# polarshield3_0c.net
KiCad netlist of a schematic drawn in EAGLE
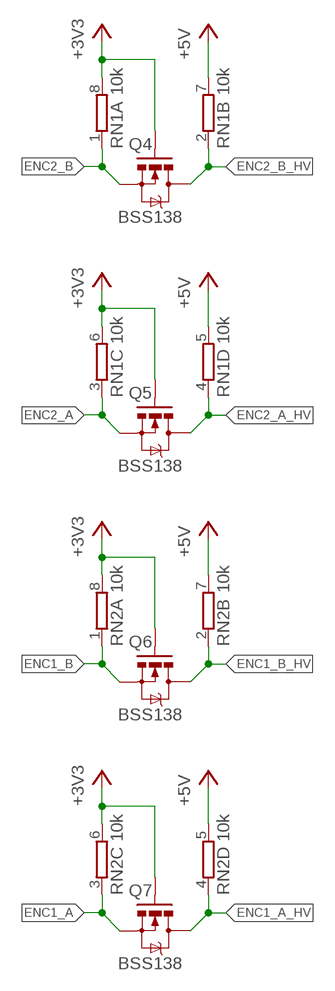
[diagram p0: schematic, sheet 1, part 1 of 2]
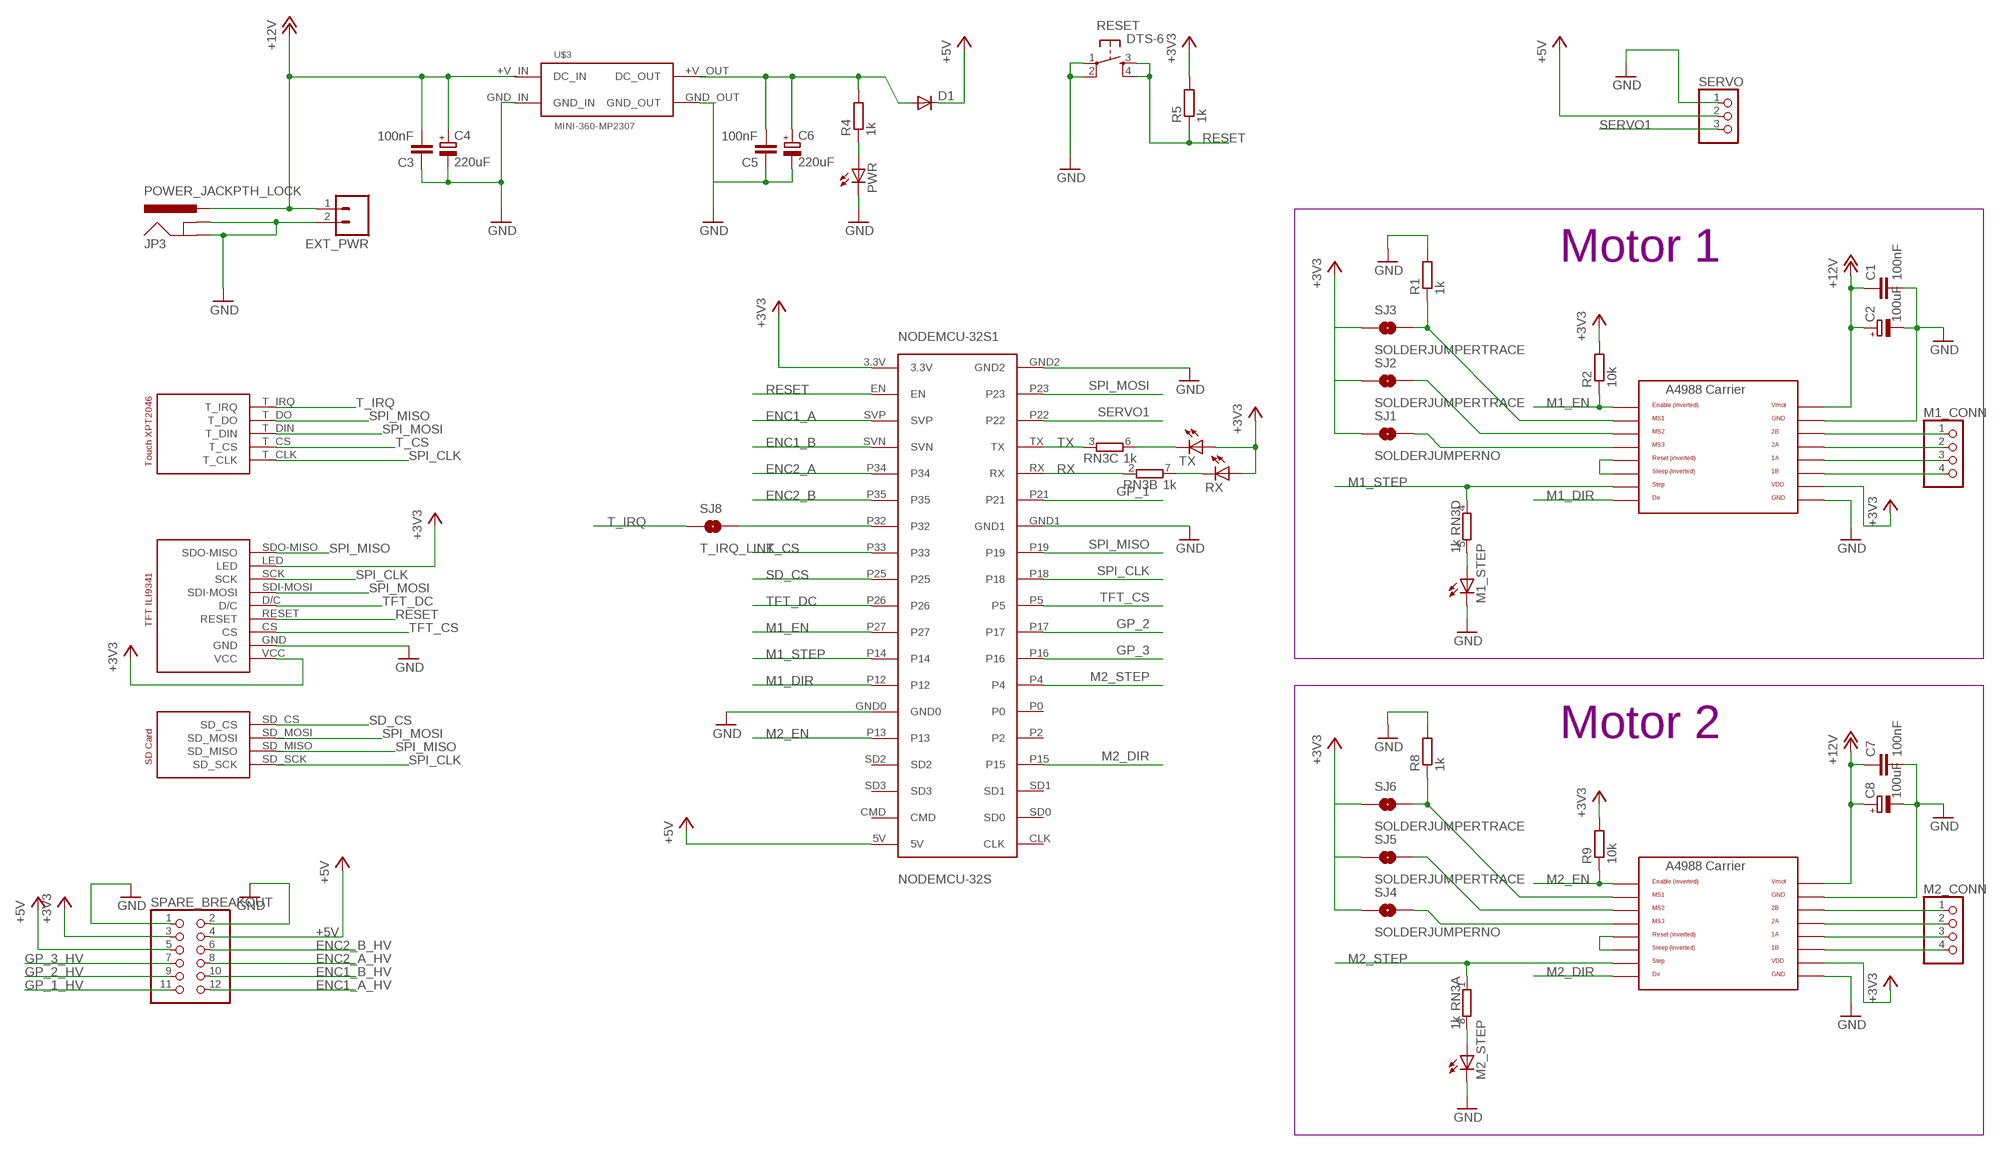
[diagram p1: schematic, sheet 1, part 2 of 2]

(export (version "E")
  (design (tool "Eeschema 10.0.6"))
  (components
    (comp (ref "C1")
      (value "100nF")
      (footprint "eagle-import:C0805")
      (libsource (lib "eagle-import") (part "C-EUC0805"))
    )
    (comp (ref "C2")
      (value "100uF")
      (footprint "eagle-import:153CLV-0605")
      (libsource (lib "eagle-import") (part "CPOL-EU153CLV-0605"))
    )
    (comp (ref "C3")
      (value "100nF")
      (footprint "eagle-import:C0805")
      (libsource (lib "eagle-import") (part "C-EUC0805"))
    )
    (comp (ref "C4")
      (value "220uF")
      (footprint "eagle-import:153CLV-0605")
      (libsource (lib "eagle-import") (part "CPOL-EU153CLV-0605"))
    )
    (comp (ref "C5")
      (value "100nF")
      (footprint "eagle-import:C0805")
      (libsource (lib "eagle-import") (part "C-EUC0805"))
    )
    (comp (ref "C6")
      (value "220uF")
      (footprint "eagle-import:153CLV-0605")
      (libsource (lib "eagle-import") (part "CPOL-EU153CLV-0605"))
    )
    (comp (ref "C7")
      (value "100nF")
      (footprint "eagle-import:C0805")
      (libsource (lib "eagle-import") (part "C-EUC0805"))
    )
    (comp (ref "C8")
      (value "100uF")
      (footprint "eagle-import:153CLV-0605")
      (libsource (lib "eagle-import") (part "CPOL-EU153CLV-0605"))
    )
    (comp (ref "D1")
      (value "DIODE-DO214BA")
      (footprint "eagle-import:DO214BA")
      (libsource (lib "eagle-import") (part "DIODE-DO214BA"))
    )
    (comp (ref "EXT_PWR")
      (value "M02PTH")
      (footprint "eagle-import:1X02")
      (libsource (lib "eagle-import") (part "M02PTH"))
    )
    (comp (ref "JP3")
      (value "POWER_JACKPTH_LOCK")
      (footprint "eagle-import:POWER_JACK_PTH_LOCK")
      (libsource (lib "eagle-import") (part "POWER_JACKPTH_LOCK"))
    )
    (comp (ref "M1_CONN")
      (value "PINHD-1X4/90")
      (footprint "eagle-import:1X04_90")
      (libsource (lib "eagle-import") (part "PINHD-1X4/90"))
    )
    (comp (ref "M1_STEP")
      (value "LEDCHIPLED_0805")
      (footprint "eagle-import:CHIPLED_0805")
      (libsource (lib "eagle-import") (part "LEDCHIPLED_0805"))
    )
    (comp (ref "M2_CONN")
      (value "PINHD-1X4/90")
      (footprint "eagle-import:1X04_90")
      (libsource (lib "eagle-import") (part "PINHD-1X4/90"))
    )
    (comp (ref "M2_STEP")
      (value "LEDCHIPLED_0805")
      (footprint "eagle-import:CHIPLED_0805")
      (libsource (lib "eagle-import") (part "LEDCHIPLED_0805"))
    )
    (comp (ref "MOTOR_1")
      (value "A4988BREAKOUT")
      (footprint "eagle-import:A4988BREAKOUT")
      (libsource (lib "eagle-import") (part "A4988BREAKOUT"))
    )
    (comp (ref "MOTOR_2")
      (value "A4988BREAKOUT")
      (footprint "eagle-import:A4988BREAKOUT")
      (libsource (lib "eagle-import") (part "A4988BREAKOUT"))
    )
    (comp (ref "NODEMCU-32S1")
      (value "NODEMCU-32S")
      (footprint "eagle-import:NODEMCU-32S")
      (libsource (lib "eagle-import") (part "NODEMCU-32S"))
    )
    (comp (ref "PWR")
      (value "LEDCHIPLED_0805")
      (footprint "eagle-import:CHIPLED_0805")
      (libsource (lib "eagle-import") (part "LEDCHIPLED_0805"))
    )
    (comp (ref "Q4")
      (value "BSS138")
      (footprint "eagle-import:SOT23-3")
      (libsource (lib "eagle-import") (part "MOSFET-NCHANNELSMD"))
    )
    (comp (ref "Q5")
      (value "BSS138")
      (footprint "eagle-import:SOT23-3")
      (libsource (lib "eagle-import") (part "MOSFET-NCHANNELSMD"))
    )
    (comp (ref "Q6")
      (value "BSS138")
      (footprint "eagle-import:SOT23-3")
      (libsource (lib "eagle-import") (part "MOSFET-NCHANNELSMD"))
    )
    (comp (ref "Q7")
      (value "BSS138")
      (footprint "eagle-import:SOT23-3")
      (libsource (lib "eagle-import") (part "MOSFET-NCHANNELSMD"))
    )
    (comp (ref "R1")
      (value "1k")
      (footprint "eagle-import:M0805")
      (libsource (lib "eagle-import") (part "R-EU_M0805"))
    )
    (comp (ref "R2")
      (value "10k")
      (footprint "eagle-import:M0805")
      (libsource (lib "eagle-import") (part "R-EU_M0805"))
    )
    (comp (ref "R4")
      (value "1k")
      (footprint "eagle-import:M0805")
      (libsource (lib "eagle-import") (part "R-EU_M0805"))
    )
    (comp (ref "R5")
      (value "1k")
      (footprint "eagle-import:M0805")
      (libsource (lib "eagle-import") (part "R-EU_M0805"))
    )
    (comp (ref "R8")
      (value "1k")
      (footprint "eagle-import:M0805")
      (libsource (lib "eagle-import") (part "R-EU_M0805"))
    )
    (comp (ref "R9")
      (value "10k")
      (footprint "eagle-import:M0805")
      (libsource (lib "eagle-import") (part "R-EU_M0805"))
    )
    (comp (ref "RESET")
      (value "DTS-6")
      (footprint "eagle-import:DTS-6")
      (libsource (lib "eagle-import") (part "DTS-6"))
    )
    (comp (ref "RN1")
      (value "10k")
      (footprint "eagle-import:EXB38V")
      (libsource (lib "eagle-import") (part "4R-NEXB38V"))
    )
    (comp (ref "RN2")
      (value "10k")
      (footprint "eagle-import:EXB38V")
      (libsource (lib "eagle-import") (part "4R-NEXB38V"))
    )
    (comp (ref "RN3")
      (value "1k")
      (footprint "eagle-import:EXB38V")
      (libsource (lib "eagle-import") (part "4R-NEXB38V"))
    )
    (comp (ref "RX")
      (value "LEDCHIPLED_0805")
      (footprint "eagle-import:CHIPLED_0805")
      (libsource (lib "eagle-import") (part "LEDCHIPLED_0805"))
    )
    (comp (ref "SERVO")
      (value "PINHD-1X3/90")
      (footprint "eagle-import:1X03_90")
      (libsource (lib "eagle-import") (part "PINHD-1X3/90"))
    )
    (comp (ref "SJ1")
      (value "SOLDERJUMPERNO")
      (footprint "eagle-import:SJ_2S-NO")
      (libsource (lib "eagle-import") (part "polargraph3_SOLDERJUMPERNO"))
    )
    (comp (ref "SJ2")
      (value "SOLDERJUMPERTRACE")
      (footprint "eagle-import:SJ_2S-TRACE")
      (libsource (lib "eagle-import") (part "polargraph3_SOLDERJUMPERTRACE"))
    )
    (comp (ref "SJ3")
      (value "SOLDERJUMPERTRACE")
      (footprint "eagle-import:SJ_2S-TRACE")
      (libsource (lib "eagle-import") (part "polargraph3_SOLDERJUMPERTRACE"))
    )
    (comp (ref "SJ4")
      (value "SOLDERJUMPERNO")
      (footprint "eagle-import:SJ_2S-NO")
      (libsource (lib "eagle-import") (part "polargraph3_SOLDERJUMPERNO"))
    )
    (comp (ref "SJ5")
      (value "SOLDERJUMPERTRACE")
      (footprint "eagle-import:SJ_2S-TRACE")
      (libsource (lib "eagle-import") (part "polargraph3_SOLDERJUMPERTRACE"))
    )
    (comp (ref "SJ6")
      (value "SOLDERJUMPERTRACE")
      (footprint "eagle-import:SJ_2S-TRACE")
      (libsource (lib "eagle-import") (part "polargraph3_SOLDERJUMPERTRACE"))
    )
    (comp (ref "SJ8")
      (value "T_IRQ_LINK")
      (footprint "eagle-import:SJ_2S-NO")
      (libsource (lib "eagle-import") (part "SOLDERJUMPERNO"))
    )
    (comp (ref "SPARE_BREAKOUT")
      (value "PINHD-2X6")
      (footprint "eagle-import:2X06")
      (libsource (lib "eagle-import") (part "PINHD-2X6"))
    )
    (comp (ref "TX")
      (value "LEDCHIPLED_0805")
      (footprint "eagle-import:CHIPLED_0805")
      (libsource (lib "eagle-import") (part "LEDCHIPLED_0805"))
    )
    (comp (ref "U$2")
      (value "2.4_TFT_SPI_TOUCH_SD")
      (footprint "eagle-import:2.4_TFT_SPI_TOUCH_SD")
      (libsource (lib "eagle-import") (part "2.4_TFT_SPI_TOUCH_SD"))
    )
    (comp (ref "U$3")
      (value "MINI-360-MP2307")
      (footprint "eagle-import:MINI-360-MP2307")
      (libsource (lib "eagle-import") (part "MINI-360-MP2307"))
    )
  )
  (nets
    (net (code "1") (name "+3V3") (class "Default")
      (node (ref "MOTOR_1") (pin "VDD") (pinfunction "VDD_VDD") (pintype "power_in"))
      (node (ref "MOTOR_2") (pin "VDD") (pinfunction "VDD_VDD") (pintype "power_in"))
      (node (ref "NODEMCU-32S1") (pin "3.3V") (pinfunction "3.3V_3.3V") (pintype "bidirectional"))
      (node (ref "Q4") (pin "1") (pinfunction "G_1") (pintype "passive"))
      (node (ref "Q5") (pin "1") (pinfunction "G_1") (pintype "passive"))
      (node (ref "Q6") (pin "1") (pinfunction "G_1") (pintype "passive"))
      (node (ref "Q7") (pin "1") (pinfunction "G_1") (pintype "passive"))
      (node (ref "R2") (pin "2") (pinfunction "2_2") (pintype "passive"))
      (node (ref "R5") (pin "2") (pinfunction "2_2") (pintype "passive"))
      (node (ref "R9") (pin "2") (pinfunction "2_2") (pintype "passive"))
      (node (ref "RN1") (pin "6") (pinfunction "2_6") (pintype "passive"))
      (node (ref "RN1") (pin "8") (pinfunction "2_8") (pintype "passive"))
      (node (ref "RN2") (pin "6") (pinfunction "2_6") (pintype "passive"))
      (node (ref "RN2") (pin "8") (pinfunction "2_8") (pintype "passive"))
      (node (ref "RX") (pin "A") (pinfunction "A_A") (pintype "passive"))
      (node (ref "SJ1") (pin "1") (pinfunction "1_1") (pintype "passive"))
      (node (ref "SJ2") (pin "1") (pinfunction "1_1") (pintype "passive"))
      (node (ref "SJ3") (pin "1") (pinfunction "1_1") (pintype "passive"))
      (node (ref "SJ4") (pin "1") (pinfunction "1_1") (pintype "passive"))
      (node (ref "SJ5") (pin "1") (pinfunction "1_1") (pintype "passive"))
      (node (ref "SJ6") (pin "1") (pinfunction "1_1") (pintype "passive"))
      (node (ref "SPARE_BREAKOUT") (pin "3") (pinfunction "3_3") (pintype "passive"))
      (node (ref "TX") (pin "A") (pinfunction "A_A") (pintype "passive"))
      (node (ref "U$2") (pin "LED") (pinfunction "LED_LED") (pintype "bidirectional"))
      (node (ref "U$2") (pin "VCC") (pinfunction "VCC_VCC") (pintype "bidirectional"))
    )
    (net (code "2") (name "+5V") (class "Default")
      (node (ref "D1") (pin "C") (pinfunction "C_C") (pintype "passive"))
      (node (ref "NODEMCU-32S1") (pin "5V") (pinfunction "5V_5V") (pintype "bidirectional"))
      (node (ref "RN1") (pin "5") (pinfunction "2_5") (pintype "passive"))
      (node (ref "RN1") (pin "7") (pinfunction "2_7") (pintype "passive"))
      (node (ref "RN2") (pin "5") (pinfunction "2_5") (pintype "passive"))
      (node (ref "RN2") (pin "7") (pinfunction "2_7") (pintype "passive"))
      (node (ref "SERVO") (pin "2") (pinfunction "2_2") (pintype "passive"))
      (node (ref "SPARE_BREAKOUT") (pin "4") (pinfunction "4_4") (pintype "passive"))
      (node (ref "SPARE_BREAKOUT") (pin "5") (pinfunction "5_5") (pintype "passive"))
    )
    (net (code "3") (name "+12V") (class "Default")
      (node (ref "C1") (pin "1") (pinfunction "1_1") (pintype "passive"))
      (node (ref "C2") (pin "+") (pinfunction "+_+") (pintype "passive"))
      (node (ref "C3") (pin "2") (pinfunction "2_2") (pintype "passive"))
      (node (ref "C4") (pin "+") (pinfunction "+_+") (pintype "passive"))
      (node (ref "C7") (pin "1") (pinfunction "1_1") (pintype "passive"))
      (node (ref "C8") (pin "+") (pinfunction "+_+") (pintype "passive"))
      (node (ref "EXT_PWR") (pin "1") (pinfunction "1_1") (pintype "passive"))
      (node (ref "JP3") (pin "PWR") (pinfunction "PWR_PWR") (pintype "bidirectional"))
      (node (ref "MOTOR_1") (pin "VMOT") (pinfunction "VMOT_VMOT") (pintype "power_in"))
      (node (ref "MOTOR_2") (pin "VMOT") (pinfunction "VMOT_VMOT") (pintype "power_in"))
      (node (ref "U$3") (pin "+V_IN") (pinfunction "DC_IN_+V_IN") (pintype "bidirectional"))
    )
    (net (code "4") (name "/GP_1") (class "Default")
      (node (ref "NODEMCU-32S1") (pin "P21") (pinfunction "P21_P21") (pintype "bidirectional"))
    )
    (net (code "5") (name "/GP_1_HV") (class "Default")
      (node (ref "SPARE_BREAKOUT") (pin "11") (pinfunction "11_11") (pintype "passive"))
    )
    (net (code "6") (name "/GP_2") (class "Default")
      (node (ref "NODEMCU-32S1") (pin "P17") (pinfunction "P17_P17") (pintype "bidirectional"))
    )
    (net (code "7") (name "/GP_2_HV") (class "Default")
      (node (ref "SPARE_BREAKOUT") (pin "9") (pinfunction "9_9") (pintype "passive"))
    )
    (net (code "8") (name "/GP_3") (class "Default")
      (node (ref "NODEMCU-32S1") (pin "P16") (pinfunction "P16_P16") (pintype "bidirectional"))
    )
    (net (code "9") (name "/GP_3_HV") (class "Default")
      (node (ref "SPARE_BREAKOUT") (pin "7") (pinfunction "7_7") (pintype "passive"))
    )
    (net (code "10") (name "/M1_DIR") (class "Default")
      (node (ref "MOTOR_1") (pin "DIR") (pinfunction "DIR_DIR") (pintype "input"))
      (node (ref "NODEMCU-32S1") (pin "P12") (pinfunction "P12_P12") (pintype "bidirectional"))
    )
    (net (code "11") (name "/M1_EN") (class "Default")
      (node (ref "MOTOR_1") (pin "EN") (pinfunction "EN_EN") (pintype "input"))
      (node (ref "NODEMCU-32S1") (pin "P27") (pinfunction "P27_P27") (pintype "bidirectional"))
      (node (ref "R2") (pin "1") (pinfunction "1_1") (pintype "passive"))
    )
    (net (code "12") (name "/M1_STEP") (class "Default")
      (node (ref "MOTOR_1") (pin "STEP") (pinfunction "STEP_STEP") (pintype "input"))
      (node (ref "NODEMCU-32S1") (pin "P14") (pinfunction "P14_P14") (pintype "bidirectional"))
      (node (ref "RN3") (pin "4") (pinfunction "1_4") (pintype "passive"))
    )
    (net (code "13") (name "/M2_DIR") (class "Default")
      (node (ref "MOTOR_2") (pin "DIR") (pinfunction "DIR_DIR") (pintype "input"))
      (node (ref "NODEMCU-32S1") (pin "P15") (pinfunction "P15_P15") (pintype "bidirectional"))
    )
    (net (code "14") (name "/M2_EN") (class "Default")
      (node (ref "MOTOR_2") (pin "EN") (pinfunction "EN_EN") (pintype "input"))
      (node (ref "NODEMCU-32S1") (pin "P13") (pinfunction "P13_P13") (pintype "bidirectional"))
      (node (ref "R9") (pin "1") (pinfunction "1_1") (pintype "passive"))
    )
    (net (code "15") (name "/M2_STEP") (class "Default")
      (node (ref "MOTOR_2") (pin "STEP") (pinfunction "STEP_STEP") (pintype "input"))
      (node (ref "NODEMCU-32S1") (pin "P4") (pinfunction "P4_P4") (pintype "bidirectional"))
      (node (ref "RN3") (pin "1") (pinfunction "1_1") (pintype "passive"))
    )
    (net (code "16") (name "/RESET") (class "Default")
      (node (ref "NODEMCU-32S1") (pin "EN") (pinfunction "EN_EN") (pintype "bidirectional"))
      (node (ref "R5") (pin "1") (pinfunction "1_1") (pintype "passive"))
      (node (ref "RESET") (pin "3") (pinfunction "3_3") (pintype "passive"))
      (node (ref "RESET") (pin "4") (pinfunction "4_4") (pintype "passive"))
      (node (ref "U$2") (pin "RESET") (pinfunction "RESET_RESET") (pintype "bidirectional"))
    )
    (net (code "17") (name "/RX") (class "Default")
      (node (ref "NODEMCU-32S1") (pin "RX") (pinfunction "RX_RX") (pintype "bidirectional"))
      (node (ref "RN3") (pin "2") (pinfunction "1_2") (pintype "passive"))
    )
    (net (code "18") (name "/SD_CS") (class "Default")
      (node (ref "NODEMCU-32S1") (pin "P25") (pinfunction "P25_P25") (pintype "bidirectional"))
      (node (ref "U$2") (pin "SD_CS") (pinfunction "SD_CS_SD_CS") (pintype "bidirectional"))
    )
    (net (code "19") (name "/SERVO1") (class "Default")
      (node (ref "NODEMCU-32S1") (pin "P22") (pinfunction "P22_P22") (pintype "bidirectional"))
      (node (ref "SERVO") (pin "3") (pinfunction "3_3") (pintype "passive"))
    )
    (net (code "20") (name "/SPI_CLK") (class "Default")
      (node (ref "NODEMCU-32S1") (pin "P18") (pinfunction "P18_P18") (pintype "bidirectional"))
      (node (ref "U$2") (pin "SCK") (pinfunction "SCK_SCK") (pintype "bidirectional"))
      (node (ref "U$2") (pin "SD_SCK") (pinfunction "SD_SCK_SD_SCK") (pintype "bidirectional"))
      (node (ref "U$2") (pin "T_CLK") (pinfunction "T_CLK_T_CLK") (pintype "input"))
    )
    (net (code "21") (name "/SPI_MISO") (class "Default")
      (node (ref "NODEMCU-32S1") (pin "P19") (pinfunction "P19_P19") (pintype "bidirectional"))
      (node (ref "U$2") (pin "SDO-MISO") (pinfunction "SDO-MISO_SDO-MISO") (pintype "bidirectional"))
      (node (ref "U$2") (pin "SD_MISO") (pinfunction "SD_MISO_SD_MISO") (pintype "bidirectional"))
      (node (ref "U$2") (pin "T_DO") (pinfunction "T_DO_T_DO") (pintype "output"))
    )
    (net (code "22") (name "/SPI_MOSI") (class "Default")
      (node (ref "NODEMCU-32S1") (pin "P23") (pinfunction "P23_P23") (pintype "bidirectional"))
      (node (ref "U$2") (pin "SDI-MOSI") (pinfunction "SDI-MOSI_SDI-MOSI") (pintype "bidirectional"))
      (node (ref "U$2") (pin "SD_MOSI") (pinfunction "SD_MOSI_SD_MOSI") (pintype "bidirectional"))
      (node (ref "U$2") (pin "T_DIN") (pinfunction "T_DIN_T_DIN") (pintype "input"))
    )
    (net (code "23") (name "/TFT_CS") (class "Default")
      (node (ref "NODEMCU-32S1") (pin "P5") (pinfunction "P5_P5") (pintype "bidirectional"))
      (node (ref "U$2") (pin "CS") (pinfunction "CS_CS") (pintype "bidirectional"))
    )
    (net (code "24") (name "/TFT_DC") (class "Default")
      (node (ref "NODEMCU-32S1") (pin "P26") (pinfunction "P26_P26") (pintype "bidirectional"))
      (node (ref "U$2") (pin "D/C") (pinfunction "D/C_D/C") (pintype "bidirectional"))
    )
    (net (code "25") (name "/TX") (class "Default")
      (node (ref "NODEMCU-32S1") (pin "TX") (pinfunction "TX_TX") (pintype "bidirectional"))
      (node (ref "RN3") (pin "3") (pinfunction "1_3") (pintype "passive"))
    )
    (net (code "26") (name "/T_CS") (class "Default")
      (node (ref "NODEMCU-32S1") (pin "P33") (pinfunction "P33_P33") (pintype "bidirectional"))
      (node (ref "U$2") (pin "T_CS") (pinfunction "T_CS_T_CS") (pintype "output"))
    )
    (net (code "27") (name "/T_IRQ") (class "Default")
      (node (ref "SJ8") (pin "1") (pinfunction "1_1") (pintype "passive"))
      (node (ref "U$2") (pin "T_IRQ") (pinfunction "T_IRQ_T_IRQ") (pintype "output"))
    )
    (net (code "28") (name "ENC1_A") (class "Default")
      (node (ref "NODEMCU-32S1") (pin "SVP") (pinfunction "SVP_SVP") (pintype "bidirectional"))
      (node (ref "Q7") (pin "2") (pinfunction "S_2") (pintype "passive"))
      (node (ref "RN2") (pin "3") (pinfunction "1_3") (pintype "passive"))
    )
    (net (code "29") (name "ENC1_A_HV") (class "Default")
      (node (ref "Q7") (pin "3") (pinfunction "D_3") (pintype "passive"))
      (node (ref "RN2") (pin "4") (pinfunction "1_4") (pintype "passive"))
      (node (ref "SPARE_BREAKOUT") (pin "12") (pinfunction "12_12") (pintype "passive"))
    )
    (net (code "30") (name "ENC1_B") (class "Default")
      (node (ref "NODEMCU-32S1") (pin "SVN") (pinfunction "SVN_SVN") (pintype "bidirectional"))
      (node (ref "Q6") (pin "2") (pinfunction "S_2") (pintype "passive"))
      (node (ref "RN2") (pin "1") (pinfunction "1_1") (pintype "passive"))
    )
    (net (code "31") (name "ENC1_B_HV") (class "Default")
      (node (ref "Q6") (pin "3") (pinfunction "D_3") (pintype "passive"))
      (node (ref "RN2") (pin "2") (pinfunction "1_2") (pintype "passive"))
      (node (ref "SPARE_BREAKOUT") (pin "10") (pinfunction "10_10") (pintype "passive"))
    )
    (net (code "32") (name "ENC2_A") (class "Default")
      (node (ref "NODEMCU-32S1") (pin "P34") (pinfunction "P34_P34") (pintype "bidirectional"))
      (node (ref "Q5") (pin "2") (pinfunction "S_2") (pintype "passive"))
      (node (ref "RN1") (pin "3") (pinfunction "1_3") (pintype "passive"))
    )
    (net (code "33") (name "ENC2_A_HV") (class "Default")
      (node (ref "Q5") (pin "3") (pinfunction "D_3") (pintype "passive"))
      (node (ref "RN1") (pin "4") (pinfunction "1_4") (pintype "passive"))
      (node (ref "SPARE_BREAKOUT") (pin "8") (pinfunction "8_8") (pintype "passive"))
    )
    (net (code "34") (name "ENC2_B") (class "Default")
      (node (ref "NODEMCU-32S1") (pin "P35") (pinfunction "P35_P35") (pintype "bidirectional"))
      (node (ref "Q4") (pin "2") (pinfunction "S_2") (pintype "passive"))
      (node (ref "RN1") (pin "1") (pinfunction "1_1") (pintype "passive"))
    )
    (net (code "35") (name "ENC2_B_HV") (class "Default")
      (node (ref "Q4") (pin "3") (pinfunction "D_3") (pintype "passive"))
      (node (ref "RN1") (pin "2") (pinfunction "1_2") (pintype "passive"))
      (node (ref "SPARE_BREAKOUT") (pin "6") (pinfunction "6_6") (pintype "passive"))
    )
    (net (code "36") (name "GND") (class "Default")
      (node (ref "C1") (pin "2") (pinfunction "2_2") (pintype "passive"))
      (node (ref "C2") (pin "-") (pinfunction "-_-") (pintype "passive"))
      (node (ref "C3") (pin "1") (pinfunction "1_1") (pintype "passive"))
      (node (ref "C4") (pin "-") (pinfunction "-_-") (pintype "passive"))
      (node (ref "C5") (pin "1") (pinfunction "1_1") (pintype "passive"))
      (node (ref "C6") (pin "-") (pinfunction "-_-") (pintype "passive"))
      (node (ref "C7") (pin "2") (pinfunction "2_2") (pintype "passive"))
      (node (ref "C8") (pin "-") (pinfunction "-_-") (pintype "passive"))
      (node (ref "EXT_PWR") (pin "2") (pinfunction "2_2") (pintype "passive"))
      (node (ref "JP3") (pin "GND") (pinfunction "GND_GND") (pintype "bidirectional"))
      (node (ref "JP3") (pin "GNDBREAK") (pinfunction "GNDBREAK_GNDBREAK") (pintype "bidirectional"))
      (node (ref "M1_STEP") (pin "C") (pinfunction "C_C") (pintype "passive"))
      (node (ref "M2_STEP") (pin "C") (pinfunction "C_C") (pintype "passive"))
      (node (ref "MOTOR_1") (pin "GND") (pinfunction "GND_GND") (pintype "power_in"))
      (node (ref "MOTOR_1") (pin "GND@0") (pinfunction "GND_GND@0") (pintype "power_in"))
      (node (ref "MOTOR_2") (pin "GND") (pinfunction "GND_GND") (pintype "power_in"))
      (node (ref "MOTOR_2") (pin "GND@0") (pinfunction "GND_GND@0") (pintype "power_in"))
      (node (ref "NODEMCU-32S1") (pin "GND0") (pinfunction "GND0_GND0") (pintype "bidirectional"))
      (node (ref "NODEMCU-32S1") (pin "GND1") (pinfunction "GND1_GND1") (pintype "bidirectional"))
      (node (ref "NODEMCU-32S1") (pin "GND2") (pinfunction "GND2_GND2") (pintype "bidirectional"))
      (node (ref "PWR") (pin "C") (pinfunction "C_C") (pintype "passive"))
      (node (ref "R1") (pin "2") (pinfunction "2_2") (pintype "passive"))
      (node (ref "R8") (pin "2") (pinfunction "2_2") (pintype "passive"))
      (node (ref "RESET") (pin "1") (pinfunction "1_1") (pintype "passive"))
      (node (ref "RESET") (pin "2") (pinfunction "2_2") (pintype "passive"))
      (node (ref "SERVO") (pin "1") (pinfunction "1_1") (pintype "passive"))
      (node (ref "SPARE_BREAKOUT") (pin "1") (pinfunction "1_1") (pintype "passive"))
      (node (ref "SPARE_BREAKOUT") (pin "2") (pinfunction "2_2") (pintype "passive"))
      (node (ref "U$2") (pin "GND") (pinfunction "GND_GND") (pintype "bidirectional"))
      (node (ref "U$3") (pin "GND_IN") (pinfunction "GND_IN_GND_IN") (pintype "bidirectional"))
      (node (ref "U$3") (pin "GND_OUT") (pinfunction "GND_OUT_GND_OUT") (pintype "bidirectional"))
    )
    (net (code "37") (name "Net-(M1_CONN-Pad1)") (class "Default")
      (node (ref "M1_CONN") (pin "1") (pinfunction "1_1") (pintype "passive"))
      (node (ref "MOTOR_1") (pin "2B") (pinfunction "2B_2B") (pintype "output"))
    )
    (net (code "38") (name "Net-(M1_CONN-Pad2)") (class "Default")
      (node (ref "M1_CONN") (pin "2") (pinfunction "2_2") (pintype "passive"))
      (node (ref "MOTOR_1") (pin "2A") (pinfunction "2A_2A") (pintype "output"))
    )
    (net (code "39") (name "Net-(M1_CONN-Pad3)") (class "Default")
      (node (ref "M1_CONN") (pin "3") (pinfunction "3_3") (pintype "passive"))
      (node (ref "MOTOR_1") (pin "1A") (pinfunction "1A_1A") (pintype "output"))
    )
    (net (code "40") (name "Net-(M1_CONN-Pad4)") (class "Default")
      (node (ref "M1_CONN") (pin "4") (pinfunction "4_4") (pintype "passive"))
      (node (ref "MOTOR_1") (pin "1B") (pinfunction "1B_1B") (pintype "output"))
    )
    (net (code "41") (name "Net-(M2_CONN-Pad1)") (class "Default")
      (node (ref "M2_CONN") (pin "1") (pinfunction "1_1") (pintype "passive"))
      (node (ref "MOTOR_2") (pin "2B") (pinfunction "2B_2B") (pintype "output"))
    )
    (net (code "42") (name "Net-(M2_CONN-Pad2)") (class "Default")
      (node (ref "M2_CONN") (pin "2") (pinfunction "2_2") (pintype "passive"))
      (node (ref "MOTOR_2") (pin "2A") (pinfunction "2A_2A") (pintype "output"))
    )
    (net (code "43") (name "Net-(M2_CONN-Pad3)") (class "Default")
      (node (ref "M2_CONN") (pin "3") (pinfunction "3_3") (pintype "passive"))
      (node (ref "MOTOR_2") (pin "1A") (pinfunction "1A_1A") (pintype "output"))
    )
    (net (code "44") (name "Net-(M2_CONN-Pad4)") (class "Default")
      (node (ref "M2_CONN") (pin "4") (pinfunction "4_4") (pintype "passive"))
      (node (ref "MOTOR_2") (pin "1B") (pinfunction "1B_1B") (pintype "output"))
    )
    (net (code "45") (name "Net-(MOTOR_1-PadMS1)") (class "Default")
      (node (ref "MOTOR_1") (pin "MS1") (pinfunction "MS1_MS1") (pintype "input"))
      (node (ref "R1") (pin "1") (pinfunction "1_1") (pintype "passive"))
      (node (ref "SJ3") (pin "2") (pinfunction "2_2") (pintype "passive"))
    )
    (net (code "46") (name "Net-(MOTOR_1-PadMS2)") (class "Default")
      (node (ref "MOTOR_1") (pin "MS2") (pinfunction "MS2_MS2") (pintype "input"))
      (node (ref "SJ2") (pin "2") (pinfunction "2_2") (pintype "passive"))
    )
    (net (code "47") (name "Net-(MOTOR_1-PadMS3)") (class "Default")
      (node (ref "MOTOR_1") (pin "MS3") (pinfunction "MS3_MS3") (pintype "input"))
      (node (ref "SJ1") (pin "2") (pinfunction "2_2") (pintype "passive"))
    )
    (net (code "48") (name "Net-(MOTOR_1-SLEEP)") (class "Default")
      (node (ref "MOTOR_1") (pin "RST") (pinfunction "RST_RST") (pintype "input"))
      (node (ref "MOTOR_1") (pin "SLP") (pinfunction "SLEEP_SLP") (pintype "input"))
    )
    (net (code "49") (name "Net-(MOTOR_2-PadMS1)") (class "Default")
      (node (ref "MOTOR_2") (pin "MS1") (pinfunction "MS1_MS1") (pintype "input"))
      (node (ref "R8") (pin "1") (pinfunction "1_1") (pintype "passive"))
      (node (ref "SJ6") (pin "2") (pinfunction "2_2") (pintype "passive"))
    )
    (net (code "50") (name "Net-(MOTOR_2-PadMS2)") (class "Default")
      (node (ref "MOTOR_2") (pin "MS2") (pinfunction "MS2_MS2") (pintype "input"))
      (node (ref "SJ5") (pin "2") (pinfunction "2_2") (pintype "passive"))
    )
    (net (code "51") (name "Net-(MOTOR_2-PadMS3)") (class "Default")
      (node (ref "MOTOR_2") (pin "MS3") (pinfunction "MS3_MS3") (pintype "input"))
      (node (ref "SJ4") (pin "2") (pinfunction "2_2") (pintype "passive"))
    )
    (net (code "52") (name "Net-(MOTOR_2-SLEEP)") (class "Default")
      (node (ref "MOTOR_2") (pin "RST") (pinfunction "RST_RST") (pintype "input"))
      (node (ref "MOTOR_2") (pin "SLP") (pinfunction "SLEEP_SLP") (pintype "input"))
    )
    (net (code "53") (name "Net-(NODEMCU-32S1-PadP32)") (class "Default")
      (node (ref "NODEMCU-32S1") (pin "P32") (pinfunction "P32_P32") (pintype "bidirectional"))
      (node (ref "SJ8") (pin "2") (pinfunction "2_2") (pintype "passive"))
    )
    (net (code "54") (name "Net-(PWR-PadA)") (class "Default")
      (node (ref "PWR") (pin "A") (pinfunction "A_A") (pintype "passive"))
      (node (ref "R4") (pin "1") (pinfunction "1_1") (pintype "passive"))
    )
    (net (code "55") (name "Net-(RN3A-2)") (class "Default")
      (node (ref "M2_STEP") (pin "A") (pinfunction "A_A") (pintype "passive"))
      (node (ref "RN3") (pin "8") (pinfunction "2_8") (pintype "passive"))
    )
    (net (code "56") (name "Net-(RN3B-2)") (class "Default")
      (node (ref "RN3") (pin "7") (pinfunction "2_7") (pintype "passive"))
      (node (ref "RX") (pin "C") (pinfunction "C_C") (pintype "passive"))
    )
    (net (code "57") (name "Net-(RN3C-2)") (class "Default")
      (node (ref "RN3") (pin "6") (pinfunction "2_6") (pintype "passive"))
      (node (ref "TX") (pin "C") (pinfunction "C_C") (pintype "passive"))
    )
    (net (code "58") (name "Net-(RN3D-2)") (class "Default")
      (node (ref "M1_STEP") (pin "A") (pinfunction "A_A") (pintype "passive"))
      (node (ref "RN3") (pin "5") (pinfunction "2_5") (pintype "passive"))
    )
    (net (code "59") (name "Net-(U$3-DC_OUT)") (class "Default")
      (node (ref "C5") (pin "2") (pinfunction "2_2") (pintype "passive"))
      (node (ref "C6") (pin "+") (pinfunction "+_+") (pintype "passive"))
      (node (ref "D1") (pin "A") (pinfunction "A_A") (pintype "passive"))
      (node (ref "R4") (pin "2") (pinfunction "2_2") (pintype "passive"))
      (node (ref "U$3") (pin "+V_OUT") (pinfunction "DC_OUT_+V_OUT") (pintype "bidirectional"))
    )
    (net (code "60") (name "unconnected-(NODEMCU-32S1-PadCLK)") (class "Default")
      (node (ref "NODEMCU-32S1") (pin "CLK") (pinfunction "CLK_CLK") (pintype "bidirectional"))
    )
    (net (code "61") (name "unconnected-(NODEMCU-32S1-PadCMD)") (class "Default")
      (node (ref "NODEMCU-32S1") (pin "CMD") (pinfunction "CMD_CMD") (pintype "bidirectional"))
    )
    (net (code "62") (name "unconnected-(NODEMCU-32S1-PadP0)") (class "Default")
      (node (ref "NODEMCU-32S1") (pin "P0") (pinfunction "P0_P0") (pintype "bidirectional"))
    )
    (net (code "63") (name "unconnected-(NODEMCU-32S1-PadP2)") (class "Default")
      (node (ref "NODEMCU-32S1") (pin "P2") (pinfunction "P2_P2") (pintype "bidirectional"))
    )
    (net (code "64") (name "unconnected-(NODEMCU-32S1-PadSD0)") (class "Default")
      (node (ref "NODEMCU-32S1") (pin "SD0") (pinfunction "SD0_SD0") (pintype "bidirectional"))
    )
    (net (code "65") (name "unconnected-(NODEMCU-32S1-PadSD1)") (class "Default")
      (node (ref "NODEMCU-32S1") (pin "SD1") (pinfunction "SD1_SD1") (pintype "bidirectional"))
    )
    (net (code "66") (name "unconnected-(NODEMCU-32S1-PadSD2)") (class "Default")
      (node (ref "NODEMCU-32S1") (pin "SD2") (pinfunction "SD2_SD2") (pintype "bidirectional"))
    )
    (net (code "67") (name "unconnected-(NODEMCU-32S1-PadSD3)") (class "Default")
      (node (ref "NODEMCU-32S1") (pin "SD3") (pinfunction "SD3_SD3") (pintype "bidirectional"))
    )
  )
)
